# Spark.net
KiCad netlist of a schematic drawn in EAGLE
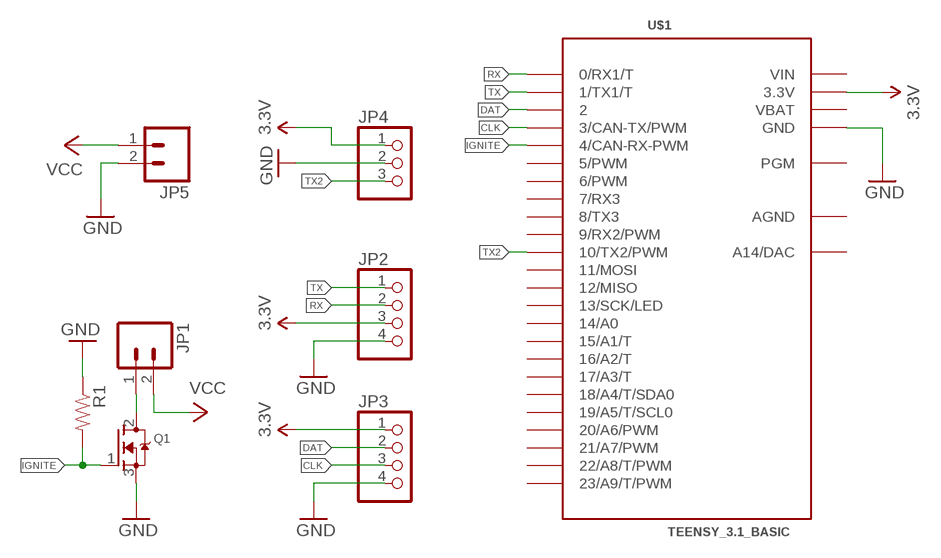
[diagram p0: schematic, sheet 1]

(export (version "E")
  (design (tool "Eeschema 10.0.6"))
  (components
    (comp (ref "JP1")
      (value "M025MM")
      (footprint "eagle-import:SCREWTERMINAL-5MM-2")
      (libsource (lib "eagle-import") (part "M025MM"))
    )
    (comp (ref "JP2")
      (value "PINHD-1X4")
      (footprint "eagle-import:1X04")
      (libsource (lib "eagle-import") (part "PINHD-1X4"))
    )
    (comp (ref "JP3")
      (value "PINHD-1X4")
      (footprint "eagle-import:1X04")
      (libsource (lib "eagle-import") (part "PINHD-1X4"))
    )
    (comp (ref "JP4")
      (value "PINHD-1X3")
      (footprint "eagle-import:1X03")
      (libsource (lib "eagle-import") (part "PINHD-1X3"))
    )
    (comp (ref "JP5")
      (value "M025MM")
      (footprint "eagle-import:SCREWTERMINAL-5MM-2")
      (libsource (lib "eagle-import") (part "M025MM"))
    )
    (comp (ref "Q1")
      (value "MOSFET-NGDS_TO220V")
      (footprint "eagle-import:TO220V")
      (libsource (lib "eagle-import") (part "MOSFET-NGDS_TO220V"))
    )
    (comp (ref "R1")
      (value "RESISTOREZ")
      (footprint "eagle-import:AXIAL-0.3EZ")
      (libsource (lib "eagle-import") (part "RESISTOREZ"))
    )
    (comp (ref "U$1")
      (value "TEENSY_3.1_BASIC")
      (footprint "eagle-import:TEENSY_3.1_BASIC")
      (libsource (lib "eagle-import") (part "TEENSY_3.1_BASIC"))
    )
  )
  (nets
    (net (code "1") (name "/AGND") (class "Default")
      (node (ref "U$1") (pin "AGND") (pinfunction "AGND_AGND") (pintype "power_in"))
    )
    (net (code "2") (name "/VBAT") (class "Default")
      (node (ref "U$1") (pin "VBAT") (pinfunction "VBAT_VBAT") (pintype "power_in"))
    )
    (net (code "3") (name "/VIN") (class "Default")
      (node (ref "U$1") (pin "VIN") (pinfunction "VIN_VIN") (pintype "power_in"))
    )
    (net (code "4") (name "3.3V") (class "Default")
      (node (ref "JP2") (pin "3") (pinfunction "3_3") (pintype "passive"))
      (node (ref "JP3") (pin "1") (pinfunction "1_1") (pintype "passive"))
      (node (ref "JP4") (pin "1") (pinfunction "1_1") (pintype "passive"))
      (node (ref "U$1") (pin "3.3V") (pinfunction "3.3V_3.3V") (pintype "power_in"))
      (node (ref "U$1") (pin "3.3V1") (pinfunction "3.3V_3.3V1") (pintype "power_in"))
    )
    (net (code "5") (name "CLK") (class "Default")
      (node (ref "JP3") (pin "3") (pinfunction "3_3") (pintype "passive"))
      (node (ref "U$1") (pin "3") (pinfunction "3/CAN-TX/PWM_3") (pintype "bidirectional"))
    )
    (net (code "6") (name "DAT") (class "Default")
      (node (ref "JP3") (pin "2") (pinfunction "2_2") (pintype "passive"))
      (node (ref "U$1") (pin "2") (pinfunction "2_2") (pintype "bidirectional"))
    )
    (net (code "7") (name "GND") (class "Default")
      (node (ref "JP2") (pin "4") (pinfunction "4_4") (pintype "passive"))
      (node (ref "JP3") (pin "4") (pinfunction "4_4") (pintype "passive"))
      (node (ref "JP4") (pin "2") (pinfunction "2_2") (pintype "passive"))
      (node (ref "JP5") (pin "2") (pinfunction "2_2") (pintype "passive"))
      (node (ref "Q1") (pin "3") (pinfunction "S_3") (pintype "bidirectional"))
      (node (ref "R1") (pin "P$1") (pinfunction "1_P$1") (pintype "passive"))
      (node (ref "U$1") (pin "GND") (pinfunction "GND_GND") (pintype "power_in"))
      (node (ref "U$1") (pin "GND1") (pinfunction "GND_GND1") (pintype "power_in"))
    )
    (net (code "8") (name "IGNITE") (class "Default")
      (node (ref "Q1") (pin "1") (pinfunction "G_1") (pintype "bidirectional"))
      (node (ref "R1") (pin "P$2") (pinfunction "2_P$2") (pintype "passive"))
      (node (ref "U$1") (pin "4") (pinfunction "4/CAN-RX-PWM_4") (pintype "bidirectional"))
    )
    (net (code "9") (name "Net-(Q1-D)") (class "Default")
      (node (ref "JP1") (pin "1") (pinfunction "1_1") (pintype "passive"))
      (node (ref "Q1") (pin "2") (pinfunction "D_2") (pintype "bidirectional"))
    )
    (net (code "10") (name "RX") (class "Default")
      (node (ref "JP2") (pin "2") (pinfunction "2_2") (pintype "passive"))
      (node (ref "U$1") (pin "0") (pinfunction "0/RX1/T_0") (pintype "bidirectional"))
    )
    (net (code "11") (name "TX") (class "Default")
      (node (ref "JP2") (pin "1") (pinfunction "1_1") (pintype "passive"))
      (node (ref "U$1") (pin "1") (pinfunction "1/TX1/T_1") (pintype "bidirectional"))
    )
    (net (code "12") (name "TX2") (class "Default")
      (node (ref "JP4") (pin "3") (pinfunction "3_3") (pintype "passive"))
      (node (ref "U$1") (pin "10") (pinfunction "10/TX2/PWM_10") (pintype "bidirectional"))
    )
    (net (code "13") (name "VCC") (class "Default")
      (node (ref "JP1") (pin "2") (pinfunction "2_2") (pintype "passive"))
      (node (ref "JP5") (pin "1") (pinfunction "1_1") (pintype "passive"))
    )
    (net (code "14") (name "unconnected-(U$1-5{slash}PWM-Pad5)") (class "Default")
      (node (ref "U$1") (pin "5") (pinfunction "5/PWM_5") (pintype "bidirectional"))
    )
    (net (code "15") (name "unconnected-(U$1-6{slash}PWM-Pad6)") (class "Default")
      (node (ref "U$1") (pin "6") (pinfunction "6/PWM_6") (pintype "bidirectional"))
    )
    (net (code "16") (name "unconnected-(U$1-7{slash}RX3-Pad7)") (class "Default")
      (node (ref "U$1") (pin "7") (pinfunction "7/RX3_7") (pintype "bidirectional"))
    )
    (net (code "17") (name "unconnected-(U$1-8{slash}TX3-Pad8)") (class "Default")
      (node (ref "U$1") (pin "8") (pinfunction "8/TX3_8") (pintype "bidirectional"))
    )
    (net (code "18") (name "unconnected-(U$1-9{slash}RX2{slash}PWM-Pad9)") (class "Default")
      (node (ref "U$1") (pin "9") (pinfunction "9/RX2/PWM_9") (pintype "bidirectional"))
    )
    (net (code "19") (name "unconnected-(U$1-11{slash}MOSI-Pad11)") (class "Default")
      (node (ref "U$1") (pin "11") (pinfunction "11/MOSI_11") (pintype "bidirectional"))
    )
    (net (code "20") (name "unconnected-(U$1-12{slash}MISO-Pad12)") (class "Default")
      (node (ref "U$1") (pin "12") (pinfunction "12/MISO_12") (pintype "bidirectional"))
    )
    (net (code "21") (name "unconnected-(U$1-13{slash}SCK{slash}LED-Pad13)") (class "Default")
      (node (ref "U$1") (pin "13") (pinfunction "13/SCK/LED_13") (pintype "bidirectional"))
    )
    (net (code "22") (name "unconnected-(U$1-15{slash}A1{slash}T-Pad15{slash}A1)") (class "Default")
      (node (ref "U$1") (pin "15/A1") (pinfunction "15/A1/T_15/A1") (pintype "bidirectional"))
    )
    (net (code "23") (name "unconnected-(U$1-16{slash}A2{slash}T-Pad16{slash}A2)") (class "Default")
      (node (ref "U$1") (pin "16/A2") (pinfunction "16/A2/T_16/A2") (pintype "bidirectional"))
    )
    (net (code "24") (name "unconnected-(U$1-17{slash}A3{slash}T-Pad17{slash}A3)") (class "Default")
      (node (ref "U$1") (pin "17/A3") (pinfunction "17/A3/T_17/A3") (pintype "bidirectional"))
    )
    (net (code "25") (name "unconnected-(U$1-18{slash}A4{slash}T{slash}SDA0-Pad18{slash}A4)") (class "Default")
      (node (ref "U$1") (pin "18/A4") (pinfunction "18/A4/T/SDA0_18/A4") (pintype "bidirectional"))
    )
    (net (code "26") (name "unconnected-(U$1-19{slash}A5{slash}T{slash}SCL0-Pad19{slash}A5)") (class "Default")
      (node (ref "U$1") (pin "19/A5") (pinfunction "19/A5/T/SCL0_19/A5") (pintype "bidirectional"))
    )
    (net (code "27") (name "unconnected-(U$1-20{slash}A6{slash}PWM-Pad20{slash}A6)") (class "Default")
      (node (ref "U$1") (pin "20/A6") (pinfunction "20/A6/PWM_20/A6") (pintype "bidirectional"))
    )
    (net (code "28") (name "unconnected-(U$1-21{slash}A7{slash}PWM-Pad21{slash}A7)") (class "Default")
      (node (ref "U$1") (pin "21/A7") (pinfunction "21/A7/PWM_21/A7") (pintype "bidirectional"))
    )
    (net (code "29") (name "unconnected-(U$1-22{slash}A8{slash}T{slash}PWM-Pad22{slash}A8)") (class "Default")
      (node (ref "U$1") (pin "22/A8") (pinfunction "22/A8/T/PWM_22/A8") (pintype "bidirectional"))
    )
    (net (code "30") (name "unconnected-(U$1-23{slash}A9{slash}T{slash}PWM-Pad23{slash}A9)") (class "Default")
      (node (ref "U$1") (pin "23/A9") (pinfunction "23/A9/T/PWM_23/A9") (pintype "bidirectional"))
    )
    (net (code "31") (name "unconnected-(U$1-A14{slash}DAC-PadA14)") (class "Default")
      (node (ref "U$1") (pin "A14") (pinfunction "A14/DAC_A14") (pintype "bidirectional"))
    )
    (net (code "32") (name "unconnected-(U$1-Pad14{slash}A0)") (class "Default")
      (node (ref "U$1") (pin "14/A0") (pinfunction "14/A0_14/A0") (pintype "bidirectional"))
    )
    (net (code "33") (name "unconnected-(U$1-PadPGM)") (class "Default")
      (node (ref "U$1") (pin "PGM") (pinfunction "PGM_PGM") (pintype "bidirectional"))
    )
  )
)
